# SCH_GSME_voltmeter_Arduino_ESP8266_TP405.net
KiCad netlist of a schematic drawn in EasyEDA
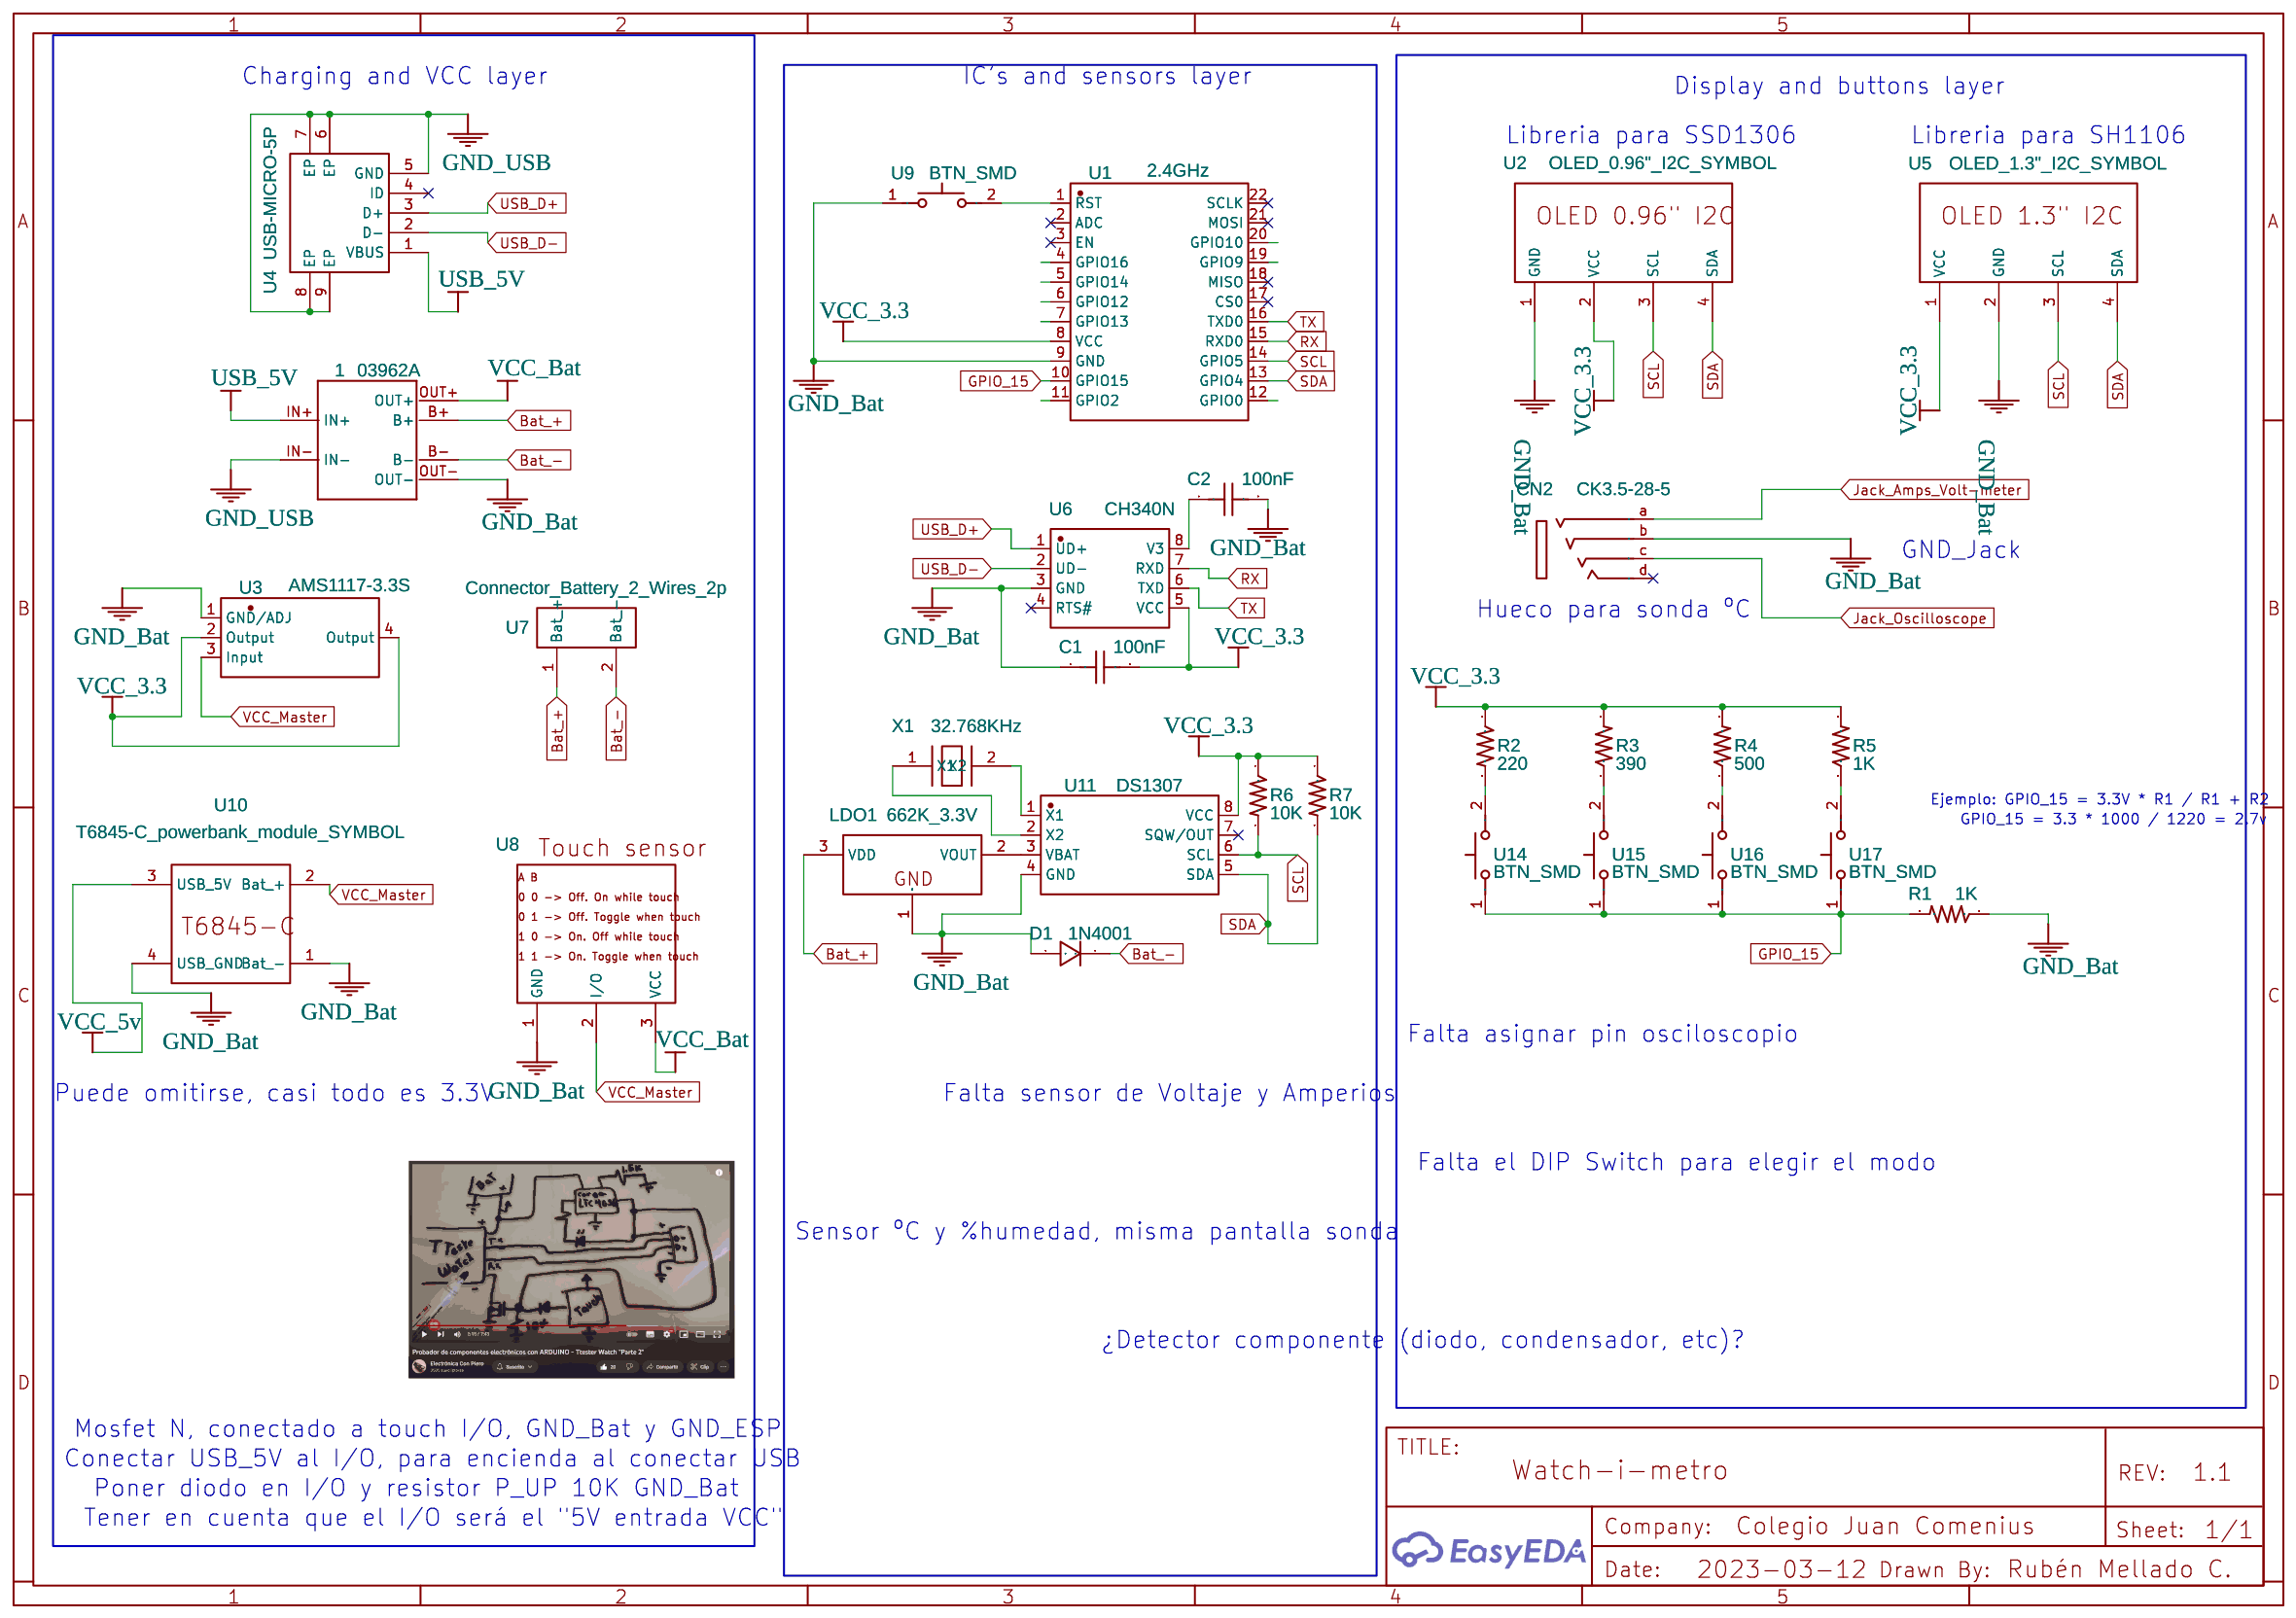
[diagram p0: schematic sheet]

(export (version "E")
  (design (tool "Eeschema 10.0.6"))
  (components
    (comp (ref "1") (value "03962A") (libsource (lib "") (part "03962A")))
    (comp (ref "C1") (value "100nF") (libsource (lib "") (part "C_0603_US")))
    (comp (ref "C2") (value "100nF") (libsource (lib "") (part "C_0603_US")))
    (comp (ref "CN2")
      (value "CK3.5-28-5")
      (fields (field (name "BOM_Supplier Part") "C718048"))
      (libsource (lib "") (part "CK3.5-28-5"))
    )
    (comp (ref "D1")
      (value "1N4001")
      (fields
        (field (name "BOM_Manufacturer Part") "1N4001-SS34")
        (field (name "BOM_Supplier Part") "C9900003229")
      )
      (libsource (lib "") (part "1N4001-SS34"))
    )
    (comp (ref "LDO1")
      (value "662K_3.3V")
      (fields
        (field (name "BOM_Manufacturer Part") "SC662K-3.3V")
        (field (name "BOM_Supplier Part") "C83932")
      )
      (libsource (lib "") (part "SC662K-3.3V"))
    )
    (comp (ref "R1") (value "1K") (libsource (lib "") (part "RESISTOR0603_2")))
    (comp (ref "R2") (value "220") (libsource (lib "") (part "RESISTOR0603")))
    (comp (ref "R3") (value "390") (libsource (lib "") (part "RESISTOR0603_1")))
    (comp (ref "R4") (value "500") (libsource (lib "") (part "RESISTOR0603_1")))
    (comp (ref "R5") (value "1K") (libsource (lib "") (part "RESISTOR0603_1")))
    (comp (ref "R6") (value "10K") (libsource (lib "") (part "RESISTOR0603")))
    (comp (ref "R7") (value "10K") (libsource (lib "") (part "RESISTOR0603")))
    (comp (ref "U1")
      (value "2.4GHz")
      (fields
        (field (name "BOM_Manufacturer Part") "ESP-12F(ESP8266MOD)")
        (field (name "BOM_Supplier Part") "C82891")
      )
      (libsource (lib "") (part "ESP-12F(ESP8266MOD)"))
    )
    (comp (ref "U2")
      (value "OLED_0.96\"_I2C_SYMBOL")
      (libsource (lib "") (part "OLED_0.96{dblquote}_I2C_SYMBOL"))
    )
    (comp (ref "U3")
      (value "AMS1117-3.3S")
      (fields (field (name "BOM_Supplier Part") "C2842296"))
      (libsource (lib "") (part "AMS1117-3.3S"))
    )
    (comp (ref "U4")
      (value "USB-MICRO-5P")
      (fields
        (field (name "BOM_Manufacturer Part") "USB-Micro-5P")
        (field (name "BOM_Supplier Part") "C9900014288")
      )
      (libsource (lib "") (part "USB-MICRO-5P"))
    )
    (comp (ref "U5")
      (value "OLED_1.3\"_I2C_SYMBOL")
      (libsource (lib "") (part "OLED_1.3{dblquote}_I2C_SYMBOL"))
    )
    (comp (ref "U6")
      (value "CH340N")
      (fields (field (name "BOM_Supplier Part") "C506813"))
      (libsource (lib "") (part "CH340N"))
    )
    (comp (ref "U7")
      (value "Connector_Battery_2_Wires_2p")
      (libsource (lib "") (part "Connector_Battery_2_Wires_2p"))
    )
    (comp (ref "U8") (value "Touch_Sensor") (libsource (lib "") (part "Touch_Sensor_3p_A_B_SYMBOL")))
    (comp (ref "U9")
      (value "BTN_SMD")
      (fields
        (field (name "BOM_Manufacturer Part") "BUTTON2")
        (field (name "BOM_Supplier Part") "C9900005988")
      )
      (libsource (lib "") (part "BUTTON2"))
    )
    (comp (ref "U10")
      (value "T6845-C_powerbank_module_SYMBOL")
      (libsource (lib "") (part "T6845-C_powerbank_module_SYMBOL"))
    )
    (comp (ref "U11")
      (value "DS1307")
      (fields
        (field (name "BOM_Manufacturer Part") "DS1307M/TR")
        (field (name "BOM_Supplier Part") "C356706")
      )
      (libsource (lib "") (part "DS1307M/TR"))
    )
    (comp (ref "U14")
      (value "BTN_SMD")
      (fields
        (field (name "BOM_Manufacturer Part") "BUTTON2")
        (field (name "BOM_Supplier Part") "C9900005988")
      )
      (libsource (lib "") (part "BUTTON2_1"))
    )
    (comp (ref "U15")
      (value "BTN_SMD")
      (fields
        (field (name "BOM_Manufacturer Part") "BUTTON2")
        (field (name "BOM_Supplier Part") "C9900005988")
      )
      (libsource (lib "") (part "BUTTON2_1"))
    )
    (comp (ref "U16")
      (value "BTN_SMD")
      (fields
        (field (name "BOM_Manufacturer Part") "BUTTON2")
        (field (name "BOM_Supplier Part") "C9900005988")
      )
      (libsource (lib "") (part "BUTTON2_1"))
    )
    (comp (ref "U17")
      (value "BTN_SMD")
      (fields
        (field (name "BOM_Manufacturer Part") "BUTTON2")
        (field (name "BOM_Supplier Part") "C9900005988")
      )
      (libsource (lib "") (part "BUTTON2_1"))
    )
    (comp (ref "X1") (value "32.768KHz") (libsource (lib "") (part "Quartz_X_2p_Symbol")))
  )
  (nets
    (net (code "1") (name "Bat_+") (class "Default")
      (node (ref "1") (pin "B+") (pinfunction "B+_B+") (pintype "bidirectional"))
      (node (ref "LDO1") (pin "3") (pinfunction "VDD_3") (pintype "unspecified"))
      (node (ref "U7") (pin "1") (pinfunction "Bat_+_1") (pintype "unspecified"))
    )
    (net (code "2") (name "Bat_-") (class "Default")
      (node (ref "1") (pin "B-") (pinfunction "B-_B-") (pintype "bidirectional"))
      (node (ref "D1") (pin "1") (pinfunction "1_1") (pintype "unspecified"))
      (node (ref "U7") (pin "2") (pinfunction "Bat_-_2") (pintype "unspecified"))
    )
    (net (code "3") (name "GND_Bat") (class "Default")
      (node (ref "1") (pin "OUT-") (pinfunction "OUT-_OUT-") (pintype "bidirectional"))
      (node (ref "C1") (pin "1") (pinfunction "1_1") (pintype "unspecified"))
      (node (ref "C2") (pin "2") (pinfunction "2_2") (pintype "unspecified"))
      (node (ref "CN2") (pin "b") (pinfunction "b_b") (pintype "unspecified"))
      (node (ref "D1") (pin "2") (pinfunction "2_2") (pintype "unspecified"))
      (node (ref "LDO1") (pin "1") (pinfunction "GND_1") (pintype "unspecified"))
      (node (ref "R1") (pin "1") (pinfunction "1_1") (pintype "unspecified"))
      (node (ref "U1") (pin "9") (pinfunction "GND_9") (pintype "unspecified"))
      (node (ref "U10") (pin "1") (pinfunction "Bat_-_1") (pintype "unspecified"))
      (node (ref "U10") (pin "4") (pinfunction "USB_GND_4") (pintype "unspecified"))
      (node (ref "U11") (pin "4") (pinfunction "GND_4") (pintype "unspecified"))
      (node (ref "U2") (pin "1") (pinfunction "GND_1") (pintype "unspecified"))
      (node (ref "U3") (pin "1") (pinfunction "GND/ADJ_1") (pintype "unspecified"))
      (node (ref "U5") (pin "2") (pinfunction "GND_2") (pintype "unspecified"))
      (node (ref "U6") (pin "3") (pinfunction "GND_3") (pintype "unspecified"))
      (node (ref "U8") (pin "1") (pinfunction "GND_1") (pintype "unspecified"))
      (node (ref "U9") (pin "1") (pinfunction "1_1") (pintype "unspecified"))
    )
    (net (code "4") (name "GND_USB") (class "Default")
      (node (ref "1") (pin "IN-") (pinfunction "IN-_IN-") (pintype "bidirectional"))
      (node (ref "U4") (pin "5") (pinfunction "GND_5") (pintype "unspecified"))
      (node (ref "U4") (pin "6") (pinfunction "EP_6") (pintype "unspecified"))
      (node (ref "U4") (pin "7") (pinfunction "EP_7") (pintype "unspecified"))
      (node (ref "U4") (pin "8") (pinfunction "EP_8") (pintype "unspecified"))
      (node (ref "U4") (pin "9") (pinfunction "EP_9") (pintype "unspecified"))
    )
    (net (code "5") (name "GPIO_15") (class "Default")
      (node (ref "R1") (pin "2") (pinfunction "2_2") (pintype "unspecified"))
      (node (ref "U1") (pin "10") (pinfunction "GPIO15_10") (pintype "unspecified"))
      (node (ref "U14") (pin "1") (pinfunction "1_1") (pintype "unspecified"))
      (node (ref "U15") (pin "1") (pinfunction "1_1") (pintype "unspecified"))
      (node (ref "U16") (pin "1") (pinfunction "1_1") (pintype "unspecified"))
      (node (ref "U17") (pin "1") (pinfunction "1_1") (pintype "unspecified"))
    )
    (net (code "6") (name "Jack_Amps_Volt-meter") (class "Default")
      (node (ref "CN2") (pin "a") (pinfunction "a_a") (pintype "unspecified"))
    )
    (net (code "7") (name "Jack_Oscilloscope") (class "Default")
      (node (ref "CN2") (pin "c") (pinfunction "c_c") (pintype "unspecified"))
    )
    (net (code "8") (name "Net-(LDO1-VOUT)") (class "Default")
      (node (ref "LDO1") (pin "2") (pinfunction "VOUT_2") (pintype "unspecified"))
      (node (ref "U11") (pin "3") (pinfunction "VBAT_3") (pintype "unspecified"))
    )
    (net (code "9") (name "Net-(R2-Pad2)") (class "Default")
      (node (ref "R2") (pin "2") (pinfunction "2_2") (pintype "unspecified"))
      (node (ref "U14") (pin "2") (pinfunction "2_2") (pintype "unspecified"))
    )
    (net (code "10") (name "Net-(R3-Pad1)") (class "Default")
      (node (ref "R3") (pin "1") (pinfunction "1_1") (pintype "unspecified"))
      (node (ref "U15") (pin "2") (pinfunction "2_2") (pintype "unspecified"))
    )
    (net (code "11") (name "Net-(R4-Pad1)") (class "Default")
      (node (ref "R4") (pin "1") (pinfunction "1_1") (pintype "unspecified"))
      (node (ref "U16") (pin "2") (pinfunction "2_2") (pintype "unspecified"))
    )
    (net (code "12") (name "Net-(R5-Pad1)") (class "Default")
      (node (ref "R5") (pin "1") (pinfunction "1_1") (pintype "unspecified"))
      (node (ref "U17") (pin "2") (pinfunction "2_2") (pintype "unspecified"))
    )
    (net (code "13") (name "Net-(U1-RST)") (class "Default")
      (node (ref "U1") (pin "1") (pinfunction "RST_1") (pintype "unspecified"))
      (node (ref "U9") (pin "2") (pinfunction "2_2") (pintype "unspecified"))
    )
    (net (code "14") (name "Net-(U6-V3)") (class "Default")
      (node (ref "C2") (pin "1") (pinfunction "1_1") (pintype "unspecified"))
      (node (ref "U6") (pin "8") (pinfunction "V3_8") (pintype "unspecified"))
    )
    (net (code "15") (name "Net-(U11-X1)") (class "Default")
      (node (ref "U11") (pin "1") (pinfunction "X1_1") (pintype "unspecified"))
      (node (ref "X1") (pin "2") (pinfunction "X2_2") (pintype "unspecified"))
    )
    (net (code "16") (name "Net-(U11-X2)") (class "Default")
      (node (ref "U11") (pin "2") (pinfunction "X2_2") (pintype "unspecified"))
      (node (ref "X1") (pin "1") (pinfunction "X1_1") (pintype "unspecified"))
    )
    (net (code "17") (name "RX") (class "Default")
      (node (ref "U1") (pin "15") (pinfunction "RXD0_15") (pintype "unspecified"))
      (node (ref "U6") (pin "7") (pinfunction "RXD_7") (pintype "unspecified"))
    )
    (net (code "18") (name "SCL") (class "Default")
      (node (ref "R6") (pin "2") (pinfunction "2_2") (pintype "unspecified"))
      (node (ref "U1") (pin "14") (pinfunction "GPIO5_14") (pintype "unspecified"))
      (node (ref "U11") (pin "6") (pinfunction "SCL_6") (pintype "unspecified"))
      (node (ref "U2") (pin "3") (pinfunction "SCL_3") (pintype "unspecified"))
      (node (ref "U5") (pin "3") (pinfunction "SCL_3") (pintype "unspecified"))
    )
    (net (code "19") (name "SDA") (class "Default")
      (node (ref "R7") (pin "2") (pinfunction "2_2") (pintype "unspecified"))
      (node (ref "U1") (pin "13") (pinfunction "GPIO4_13") (pintype "unspecified"))
      (node (ref "U11") (pin "5") (pinfunction "SDA_5") (pintype "unspecified"))
      (node (ref "U2") (pin "4") (pinfunction "SDA_4") (pintype "unspecified"))
      (node (ref "U5") (pin "4") (pinfunction "SDA_4") (pintype "unspecified"))
    )
    (net (code "20") (name "TX") (class "Default")
      (node (ref "U1") (pin "16") (pinfunction "TXD0_16") (pintype "unspecified"))
      (node (ref "U6") (pin "6") (pinfunction "TXD_6") (pintype "unspecified"))
    )
    (net (code "21") (name "USB_5V") (class "Default")
      (node (ref "1") (pin "IN+") (pinfunction "IN+_IN+") (pintype "bidirectional"))
      (node (ref "U4") (pin "1") (pinfunction "VBUS_1") (pintype "unspecified"))
    )
    (net (code "22") (name "USB_D+") (class "Default")
      (node (ref "U4") (pin "3") (pinfunction "D+_3") (pintype "unspecified"))
      (node (ref "U6") (pin "1") (pinfunction "UD+_1") (pintype "unspecified"))
    )
    (net (code "23") (name "USB_D-") (class "Default")
      (node (ref "U4") (pin "2") (pinfunction "D-_2") (pintype "unspecified"))
      (node (ref "U6") (pin "2") (pinfunction "UD-_2") (pintype "unspecified"))
    )
    (net (code "24") (name "VCC_3.3") (class "Default")
      (node (ref "C1") (pin "2") (pinfunction "2_2") (pintype "unspecified"))
      (node (ref "R2") (pin "1") (pinfunction "1_1") (pintype "unspecified"))
      (node (ref "R3") (pin "2") (pinfunction "2_2") (pintype "unspecified"))
      (node (ref "R4") (pin "2") (pinfunction "2_2") (pintype "unspecified"))
      (node (ref "R5") (pin "2") (pinfunction "2_2") (pintype "unspecified"))
      (node (ref "R6") (pin "1") (pinfunction "1_1") (pintype "unspecified"))
      (node (ref "R7") (pin "1") (pinfunction "1_1") (pintype "unspecified"))
      (node (ref "U1") (pin "8") (pinfunction "VCC_8") (pintype "unspecified"))
      (node (ref "U11") (pin "8") (pinfunction "VCC_8") (pintype "unspecified"))
      (node (ref "U2") (pin "2") (pinfunction "VCC_2") (pintype "unspecified"))
      (node (ref "U3") (pin "2") (pinfunction "Output_2") (pintype "unspecified"))
      (node (ref "U3") (pin "4") (pinfunction "Output_4") (pintype "unspecified"))
      (node (ref "U5") (pin "1") (pinfunction "VCC_1") (pintype "unspecified"))
      (node (ref "U6") (pin "5") (pinfunction "VCC_5") (pintype "unspecified"))
    )
    (net (code "25") (name "VCC_5v") (class "Default")
      (node (ref "U10") (pin "3") (pinfunction "USB_5V_3") (pintype "unspecified"))
    )
    (net (code "26") (name "VCC_Bat") (class "Default")
      (node (ref "1") (pin "OUT+") (pinfunction "OUT+_OUT+") (pintype "bidirectional"))
      (node (ref "U8") (pin "3") (pinfunction "VCC_3") (pintype "unspecified"))
    )
    (net (code "27") (name "VCC_Master") (class "Default")
      (node (ref "U10") (pin "2") (pinfunction "Bat_+_2") (pintype "unspecified"))
      (node (ref "U3") (pin "3") (pinfunction "Input_3") (pintype "unspecified"))
      (node (ref "U8") (pin "2") (pinfunction "I/O_2") (pintype "unspecified"))
    )
    (net (code "28") (name "unconnected-(CN2-Padd)") (class "Default")
      (node (ref "CN2") (pin "d") (pinfunction "d_d") (pintype "unspecified+no_connect"))
    )
    (net (code "29") (name "unconnected-(U1-ADC-Pad2)") (class "Default")
      (node (ref "U1") (pin "2") (pinfunction "ADC_2") (pintype "unspecified+no_connect"))
    )
    (net (code "30") (name "unconnected-(U1-CS0-Pad17)") (class "Default")
      (node (ref "U1") (pin "17") (pinfunction "CS0_17") (pintype "unspecified+no_connect"))
    )
    (net (code "31") (name "unconnected-(U1-EN-Pad3)") (class "Default")
      (node (ref "U1") (pin "3") (pinfunction "EN_3") (pintype "unspecified+no_connect"))
    )
    (net (code "32") (name "unconnected-(U1-GPIO0-Pad12)") (class "Default")
      (node (ref "U1") (pin "12") (pinfunction "GPIO0_12") (pintype "unspecified"))
    )
    (net (code "33") (name "unconnected-(U1-GPIO2-Pad11)") (class "Default")
      (node (ref "U1") (pin "11") (pinfunction "GPIO2_11") (pintype "unspecified"))
    )
    (net (code "34") (name "unconnected-(U1-GPIO9-Pad19)") (class "Default")
      (node (ref "U1") (pin "19") (pinfunction "GPIO9_19") (pintype "unspecified"))
    )
    (net (code "35") (name "unconnected-(U1-GPIO10-Pad20)") (class "Default")
      (node (ref "U1") (pin "20") (pinfunction "GPIO10_20") (pintype "unspecified"))
    )
    (net (code "36") (name "unconnected-(U1-GPIO12-Pad6)") (class "Default")
      (node (ref "U1") (pin "6") (pinfunction "GPIO12_6") (pintype "unspecified"))
    )
    (net (code "37") (name "unconnected-(U1-GPIO13-Pad7)") (class "Default")
      (node (ref "U1") (pin "7") (pinfunction "GPIO13_7") (pintype "unspecified"))
    )
    (net (code "38") (name "unconnected-(U1-GPIO14-Pad5)") (class "Default")
      (node (ref "U1") (pin "5") (pinfunction "GPIO14_5") (pintype "unspecified"))
    )
    (net (code "39") (name "unconnected-(U1-GPIO16-Pad4)") (class "Default")
      (node (ref "U1") (pin "4") (pinfunction "GPIO16_4") (pintype "unspecified"))
    )
    (net (code "40") (name "unconnected-(U1-MISO-Pad18)") (class "Default")
      (node (ref "U1") (pin "18") (pinfunction "MISO_18") (pintype "unspecified+no_connect"))
    )
    (net (code "41") (name "unconnected-(U1-MOSI-Pad21)") (class "Default")
      (node (ref "U1") (pin "21") (pinfunction "MOSI_21") (pintype "unspecified+no_connect"))
    )
    (net (code "42") (name "unconnected-(U1-SCLK-Pad22)") (class "Default")
      (node (ref "U1") (pin "22") (pinfunction "SCLK_22") (pintype "unspecified+no_connect"))
    )
    (net (code "43") (name "unconnected-(U4-ID-Pad4)") (class "Default")
      (node (ref "U4") (pin "4") (pinfunction "ID_4") (pintype "unspecified+no_connect"))
    )
    (net (code "44") (name "unconnected-(U6-RTS#-Pad4)") (class "Default")
      (node (ref "U6") (pin "4") (pinfunction "RTS#_4") (pintype "unspecified+no_connect"))
    )
    (net (code "45") (name "unconnected-(U11-SQW{slash}OUT-Pad7)") (class "Default")
      (node (ref "U11") (pin "7") (pinfunction "SQW/OUT_7") (pintype "unspecified+no_connect"))
    )
  )
)
